# nRF52810_qcaa_dcdc.net
KiCad netlist of a schematic drawn in EAGLE
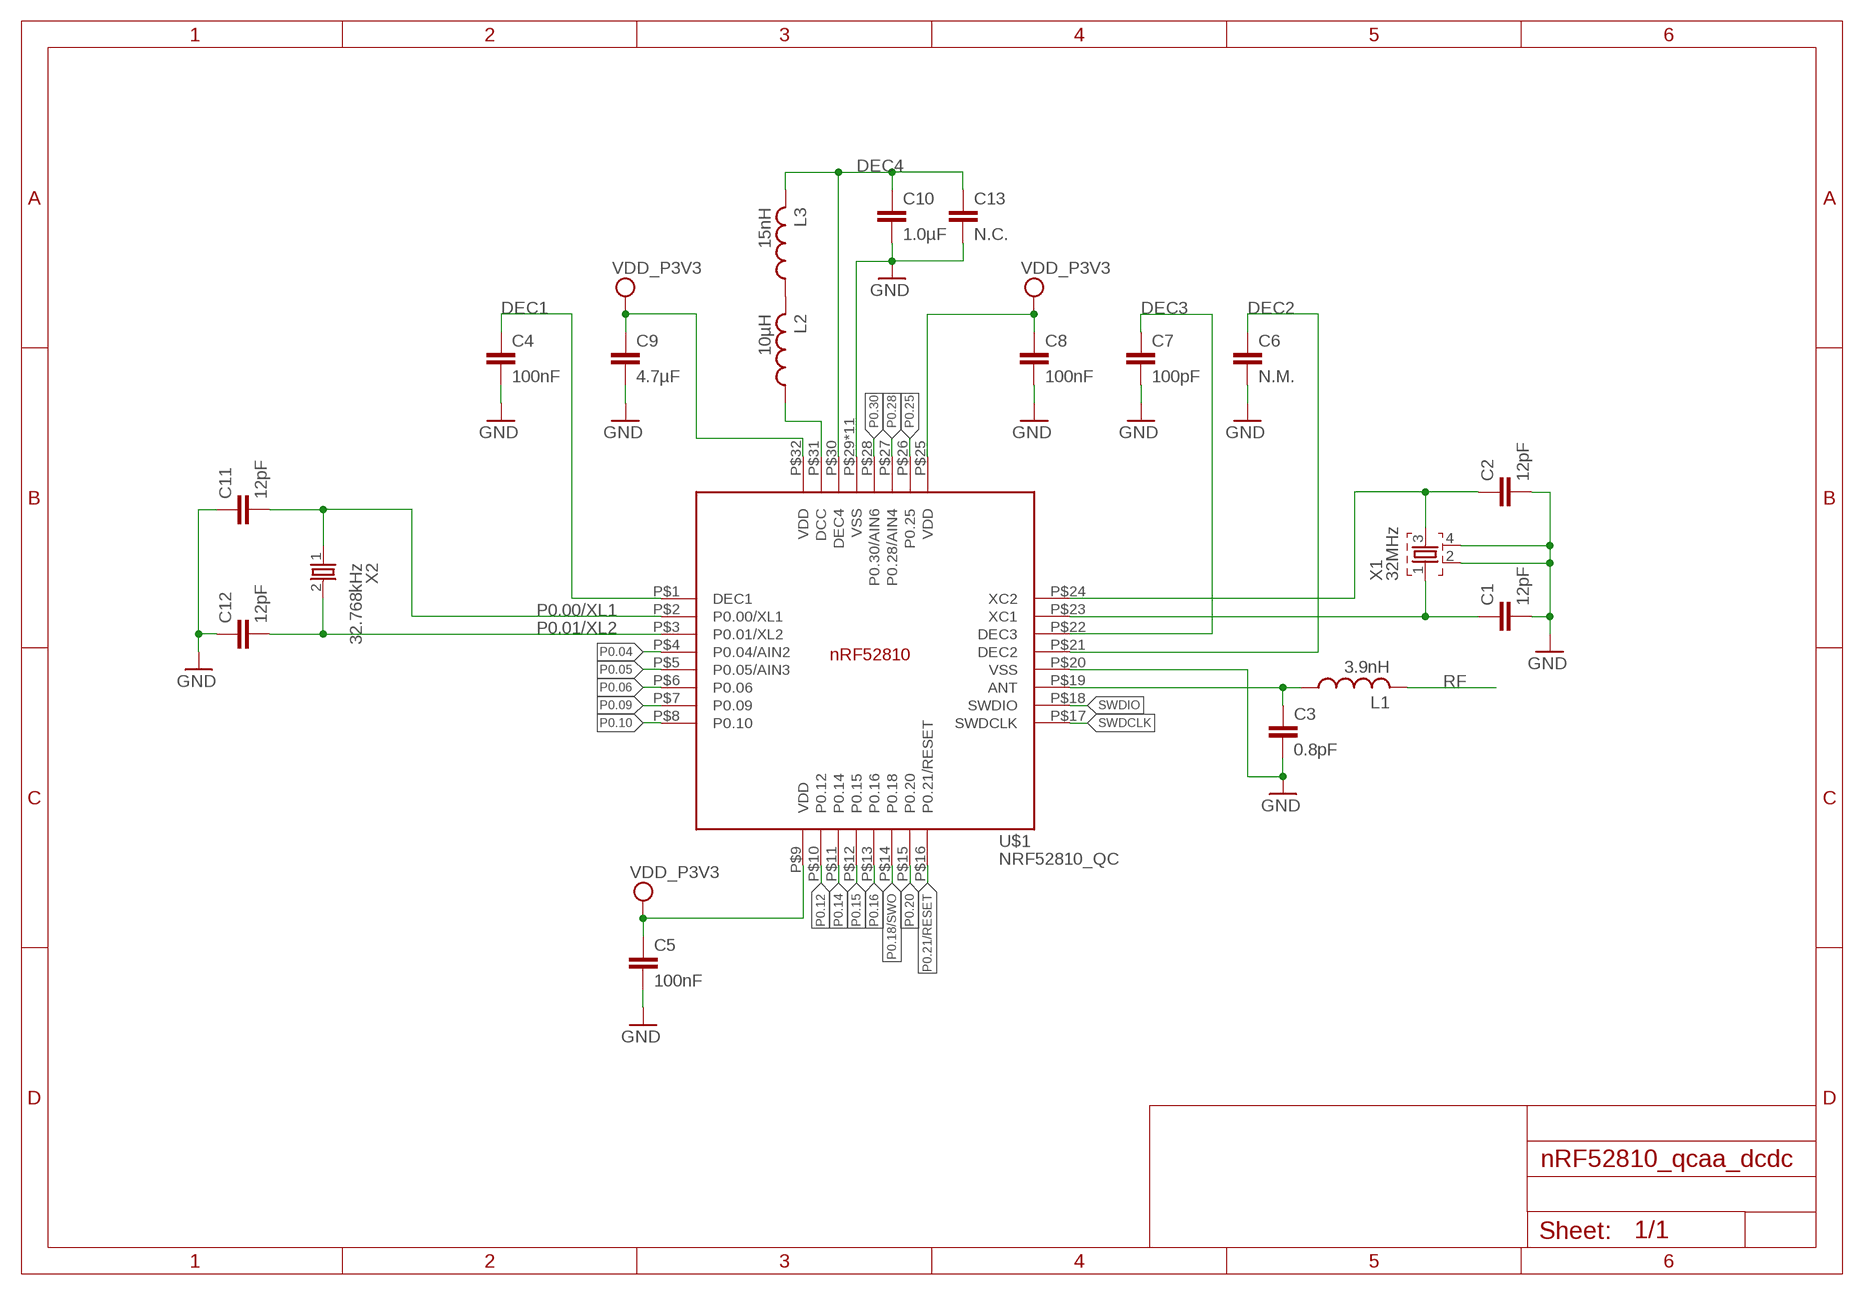
[diagram p0: schematic, sheet 1]

(export (version "E")
  (design (tool "Eeschema 10.0.6"))
  (components
    (comp (ref "C1")
      (value "12pF")
      (footprint "eagle-import:RESC0402_N")
      (libsource (lib "eagle-import") (part "CAPACITOR_0402_N"))
    )
    (comp (ref "C2")
      (value "12pF")
      (footprint "eagle-import:RESC0402_N")
      (libsource (lib "eagle-import") (part "CAPACITOR_0402_N"))
    )
    (comp (ref "C3")
      (value "0.8pF")
      (footprint "eagle-import:RESC0402_N")
      (libsource (lib "eagle-import") (part "CAPACITOR_0402_N"))
    )
    (comp (ref "C4")
      (value "100nF")
      (footprint "eagle-import:RESC0402_N")
      (libsource (lib "eagle-import") (part "CAPACITOR_0402_N"))
    )
    (comp (ref "C5")
      (value "100nF")
      (footprint "eagle-import:RESC0402_N")
      (libsource (lib "eagle-import") (part "CAPACITOR_0402_N"))
    )
    (comp (ref "C6")
      (value "N.M.")
      (footprint "eagle-import:RESC0402_N")
      (libsource (lib "eagle-import") (part "CAPACITOR_0402_N"))
    )
    (comp (ref "C7")
      (value "100pF")
      (footprint "eagle-import:RESC0402_N")
      (libsource (lib "eagle-import") (part "CAPACITOR_0402_N"))
    )
    (comp (ref "C8")
      (value "100nF")
      (footprint "eagle-import:RESC0402_N")
      (libsource (lib "eagle-import") (part "CAPACITOR_0402_N"))
    )
    (comp (ref "C9")
      (value "4.7µF")
      (footprint "eagle-import:RESC0603_N")
      (libsource (lib "eagle-import") (part "CAPACITOR_0603_N"))
    )
    (comp (ref "C10")
      (value "1.0µF")
      (footprint "eagle-import:RESC0603_N")
      (libsource (lib "eagle-import") (part "CAPACITOR_0603_N"))
    )
    (comp (ref "C11")
      (value "12pF")
      (footprint "eagle-import:RESC0402_N")
      (libsource (lib "eagle-import") (part "CAPACITOR_0402_N"))
    )
    (comp (ref "C12")
      (value "12pF")
      (footprint "eagle-import:RESC0402_N")
      (libsource (lib "eagle-import") (part "CAPACITOR_0402_N"))
    )
    (comp (ref "C13")
      (value "N.C.")
      (footprint "eagle-import:RESC0402_N")
      (libsource (lib "eagle-import") (part "CAPACITOR_0402_N"))
    )
    (comp (ref "L1")
      (value "3.9nH")
      (footprint "eagle-import:RESC0402_N")
      (libsource (lib "eagle-import") (part "INDUCTOR_0402_N"))
    )
    (comp (ref "L2")
      (value "10µH")
      (footprint "eagle-import:RESC0603_N")
      (libsource (lib "eagle-import") (part "INDUCTOR_0603_N"))
    )
    (comp (ref "L3")
      (value "15nH")
      (footprint "eagle-import:RESC0402_N")
      (libsource (lib "eagle-import") (part "INDUCTOR_0402_N"))
    )
    (comp (ref "U$1")
      (value "NRF52810_QC")
      (footprint "eagle-import:QFN50P500X500X90-32_N")
      (libsource (lib "eagle-import") (part "NRF52810_QC"))
    )
    (comp (ref "X1")
      (value "32MHz")
      (footprint "eagle-import:BT-XTAL_2016_N")
      (libsource (lib "eagle-import") (part "XTAL_32MHZ"))
    )
    (comp (ref "X2")
      (value "32.768kHz")
      (footprint "eagle-import:XTAL_3215_N")
      (libsource (lib "eagle-import") (part "XTAL_32KHZ"))
    )
  )
  (nets
    (net (code "1") (name "/DEC1") (class "Default")
      (node (ref "C4") (pin "1") (pinfunction "1_1") (pintype "passive"))
      (node (ref "U$1") (pin "P$1") (pinfunction "DEC1_P$1") (pintype "bidirectional"))
    )
    (net (code "2") (name "/DEC2") (class "Default")
      (node (ref "C6") (pin "1") (pinfunction "1_1") (pintype "passive"))
      (node (ref "U$1") (pin "P$21") (pinfunction "DEC2_P$21") (pintype "bidirectional"))
    )
    (net (code "3") (name "/DEC3") (class "Default")
      (node (ref "C7") (pin "1") (pinfunction "1_1") (pintype "passive"))
      (node (ref "U$1") (pin "P$22") (pinfunction "DEC3_P$22") (pintype "bidirectional"))
    )
    (net (code "4") (name "/DEC4") (class "Default")
      (node (ref "C10") (pin "1") (pinfunction "1_1") (pintype "passive"))
      (node (ref "C13") (pin "1") (pinfunction "1_1") (pintype "passive"))
      (node (ref "L3") (pin "2") (pinfunction "2_2") (pintype "passive"))
      (node (ref "U$1") (pin "P$30") (pinfunction "DEC4_P$30") (pintype "bidirectional"))
    )
    (net (code "5") (name "/P0.00{slash}XL1") (class "Default")
      (node (ref "C11") (pin "2") (pinfunction "2_2") (pintype "passive"))
      (node (ref "U$1") (pin "P$2") (pinfunction "P0.00/XL1_P$2") (pintype "bidirectional"))
      (node (ref "X2") (pin "1") (pinfunction "1_1") (pintype "passive"))
    )
    (net (code "6") (name "/P0.01{slash}XL2") (class "Default")
      (node (ref "C12") (pin "2") (pinfunction "2_2") (pintype "passive"))
      (node (ref "U$1") (pin "P$3") (pinfunction "P0.01/XL2_P$3") (pintype "bidirectional"))
      (node (ref "X2") (pin "2") (pinfunction "2_2") (pintype "passive"))
    )
    (net (code "7") (name "/RF") (class "Default")
      (node (ref "L1") (pin "2") (pinfunction "2_2") (pintype "passive"))
    )
    (net (code "8") (name "GND") (class "Default")
      (node (ref "C1") (pin "2") (pinfunction "2_2") (pintype "passive"))
      (node (ref "C10") (pin "2") (pinfunction "2_2") (pintype "passive"))
      (node (ref "C11") (pin "1") (pinfunction "1_1") (pintype "passive"))
      (node (ref "C12") (pin "1") (pinfunction "1_1") (pintype "passive"))
      (node (ref "C13") (pin "2") (pinfunction "2_2") (pintype "passive"))
      (node (ref "C2") (pin "2") (pinfunction "2_2") (pintype "passive"))
      (node (ref "C3") (pin "2") (pinfunction "2_2") (pintype "passive"))
      (node (ref "C4") (pin "2") (pinfunction "2_2") (pintype "passive"))
      (node (ref "C5") (pin "2") (pinfunction "2_2") (pintype "passive"))
      (node (ref "C6") (pin "2") (pinfunction "2_2") (pintype "passive"))
      (node (ref "C7") (pin "2") (pinfunction "2_2") (pintype "passive"))
      (node (ref "C8") (pin "2") (pinfunction "2_2") (pintype "passive"))
      (node (ref "C9") (pin "2") (pinfunction "2_2") (pintype "passive"))
      (node (ref "U$1") (pin "P$20") (pinfunction "VSS_P$20") (pintype "bidirectional"))
      (node (ref "U$1") (pin "P$29") (pinfunction "VSS_P$29") (pintype "bidirectional"))
      (node (ref "U$1") (pin "P$33") (pinfunction "VSS_P$33") (pintype "bidirectional"))
      (node (ref "U$1") (pin "P$34") (pinfunction "VSS_P$34") (pintype "bidirectional"))
      (node (ref "U$1") (pin "P$35") (pinfunction "VSS_P$35") (pintype "bidirectional"))
      (node (ref "U$1") (pin "P$36") (pinfunction "VSS_P$36") (pintype "bidirectional"))
      (node (ref "U$1") (pin "P$37") (pinfunction "VSS_P$37") (pintype "bidirectional"))
      (node (ref "U$1") (pin "P$38") (pinfunction "VSS_P$38") (pintype "bidirectional"))
      (node (ref "U$1") (pin "P$39") (pinfunction "VSS_P$39") (pintype "bidirectional"))
      (node (ref "U$1") (pin "P$40") (pinfunction "VSS_P$40") (pintype "bidirectional"))
      (node (ref "U$1") (pin "P$41") (pinfunction "VSS_P$41") (pintype "bidirectional"))
      (node (ref "U$1") (pin "P$42") (pinfunction "VSS_P$42") (pintype "bidirectional"))
      (node (ref "X1") (pin "2") (pinfunction "2_2") (pintype "passive"))
      (node (ref "X1") (pin "4") (pinfunction "4_4") (pintype "passive"))
    )
    (net (code "9") (name "Net-(L2-Pad2)") (class "Default")
      (node (ref "L2") (pin "2") (pinfunction "2_2") (pintype "passive"))
      (node (ref "L3") (pin "1") (pinfunction "1_1") (pintype "passive"))
    )
    (net (code "10") (name "Net-(U$1-ANT)") (class "Default")
      (node (ref "C3") (pin "1") (pinfunction "1_1") (pintype "passive"))
      (node (ref "L1") (pin "1") (pinfunction "1_1") (pintype "passive"))
      (node (ref "U$1") (pin "P$19") (pinfunction "ANT_P$19") (pintype "bidirectional"))
    )
    (net (code "11") (name "Net-(U$1-DCC)") (class "Default")
      (node (ref "L2") (pin "1") (pinfunction "1_1") (pintype "passive"))
      (node (ref "U$1") (pin "P$31") (pinfunction "DCC_P$31") (pintype "bidirectional"))
    )
    (net (code "12") (name "Net-(U$1-XC1)") (class "Default")
      (node (ref "C1") (pin "1") (pinfunction "1_1") (pintype "passive"))
      (node (ref "U$1") (pin "P$23") (pinfunction "XC1_P$23") (pintype "bidirectional"))
      (node (ref "X1") (pin "1") (pinfunction "1_1") (pintype "passive"))
    )
    (net (code "13") (name "Net-(U$1-XC2)") (class "Default")
      (node (ref "C2") (pin "1") (pinfunction "1_1") (pintype "passive"))
      (node (ref "U$1") (pin "P$24") (pinfunction "XC2_P$24") (pintype "bidirectional"))
      (node (ref "X1") (pin "3") (pinfunction "3_3") (pintype "passive"))
    )
    (net (code "14") (name "P0.04") (class "Default")
      (node (ref "U$1") (pin "P$4") (pinfunction "P0.04/AIN2_P$4") (pintype "bidirectional"))
    )
    (net (code "15") (name "P0.05") (class "Default")
      (node (ref "U$1") (pin "P$5") (pinfunction "P0.05/AIN3_P$5") (pintype "bidirectional"))
    )
    (net (code "16") (name "P0.06") (class "Default")
      (node (ref "U$1") (pin "P$6") (pinfunction "P0.06_P$6") (pintype "bidirectional"))
    )
    (net (code "17") (name "P0.09") (class "Default")
      (node (ref "U$1") (pin "P$7") (pinfunction "P0.09_P$7") (pintype "bidirectional"))
    )
    (net (code "18") (name "P0.10") (class "Default")
      (node (ref "U$1") (pin "P$8") (pinfunction "P0.10_P$8") (pintype "bidirectional"))
    )
    (net (code "19") (name "P0.12") (class "Default")
      (node (ref "U$1") (pin "P$10") (pinfunction "P0.12_P$10") (pintype "bidirectional"))
    )
    (net (code "20") (name "P0.14") (class "Default")
      (node (ref "U$1") (pin "P$11") (pinfunction "P0.14_P$11") (pintype "bidirectional"))
    )
    (net (code "21") (name "P0.15") (class "Default")
      (node (ref "U$1") (pin "P$12") (pinfunction "P0.15_P$12") (pintype "bidirectional"))
    )
    (net (code "22") (name "P0.16") (class "Default")
      (node (ref "U$1") (pin "P$13") (pinfunction "P0.16_P$13") (pintype "bidirectional"))
    )
    (net (code "23") (name "P0.18{slash}SWO") (class "Default")
      (node (ref "U$1") (pin "P$14") (pinfunction "P0.18_P$14") (pintype "bidirectional"))
    )
    (net (code "24") (name "P0.20") (class "Default")
      (node (ref "U$1") (pin "P$15") (pinfunction "P0.20_P$15") (pintype "bidirectional"))
    )
    (net (code "25") (name "P0.21{slash}RESET") (class "Default")
      (node (ref "U$1") (pin "P$16") (pinfunction "P0.21/RESET_P$16") (pintype "bidirectional"))
    )
    (net (code "26") (name "P0.25") (class "Default")
      (node (ref "U$1") (pin "P$26") (pinfunction "P0.25_P$26") (pintype "bidirectional"))
    )
    (net (code "27") (name "P0.28") (class "Default")
      (node (ref "U$1") (pin "P$27") (pinfunction "P0.28/AIN4_P$27") (pintype "bidirectional"))
    )
    (net (code "28") (name "P0.30") (class "Default")
      (node (ref "U$1") (pin "P$28") (pinfunction "P0.30/AIN6_P$28") (pintype "bidirectional"))
    )
    (net (code "29") (name "SWDCLK") (class "Default")
      (node (ref "U$1") (pin "P$17") (pinfunction "SWDCLK_P$17") (pintype "bidirectional"))
    )
    (net (code "30") (name "SWDIO") (class "Default")
      (node (ref "U$1") (pin "P$18") (pinfunction "SWDIO_P$18") (pintype "bidirectional"))
    )
    (net (code "31") (name "VDD_P3V3") (class "Default")
      (node (ref "C5") (pin "1") (pinfunction "1_1") (pintype "passive"))
      (node (ref "C8") (pin "1") (pinfunction "1_1") (pintype "passive"))
      (node (ref "C9") (pin "1") (pinfunction "1_1") (pintype "passive"))
      (node (ref "U$1") (pin "P$25") (pinfunction "VDD_P$25") (pintype "bidirectional"))
      (node (ref "U$1") (pin "P$32") (pinfunction "VDD_P$32") (pintype "bidirectional"))
      (node (ref "U$1") (pin "P$9") (pinfunction "VDD_P$9") (pintype "bidirectional"))
    )
  )
)
